# GSServer.net
KiCad netlist of a schematic drawn in EAGLE
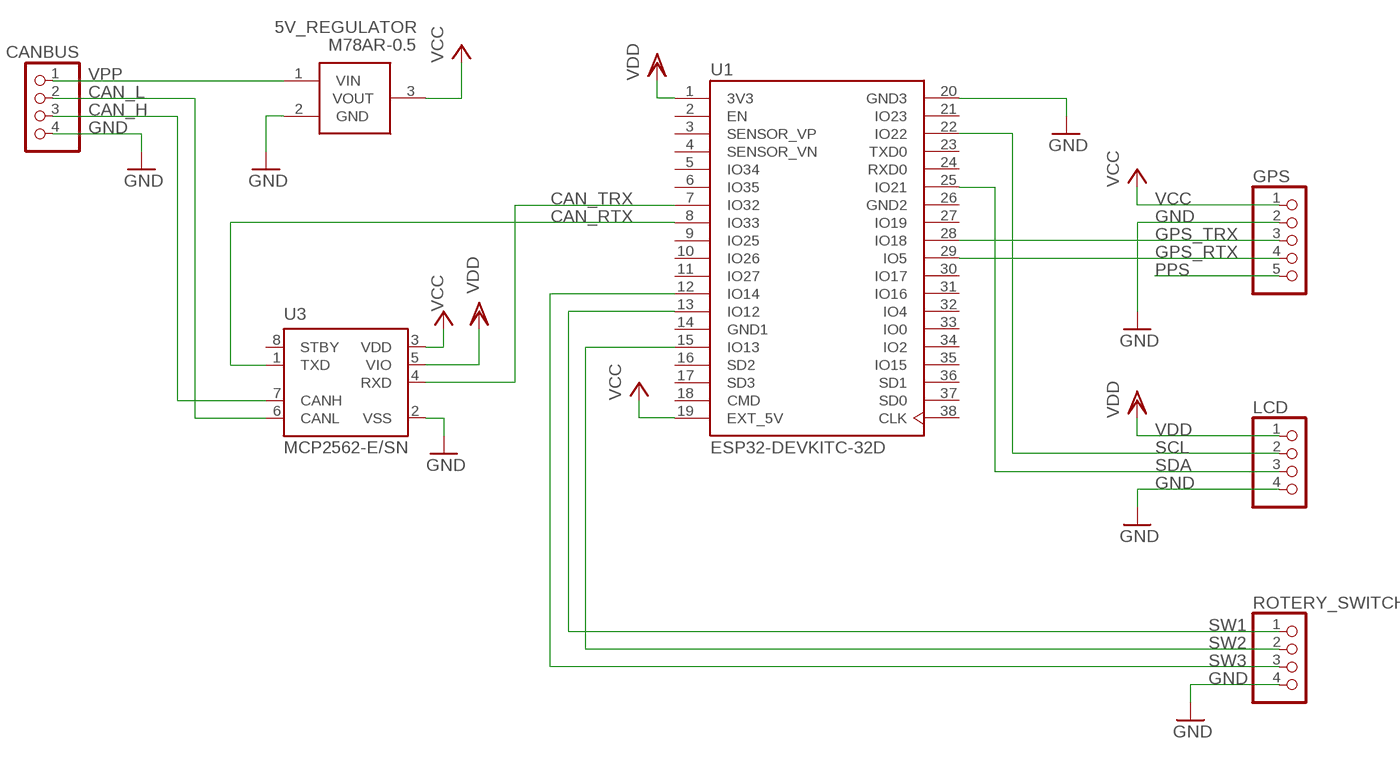
[diagram p0: schematic, sheet 1]

(export (version "E")
  (design (tool "Eeschema 10.0.6"))
  (components
    (comp (ref "5V_REGULATOR")
      (value "M78AR-0.5")
      (footprint "eagle-import:SHDR3W75P0X254_1X3_1128X755X10")
      (libsource (lib "eagle-import") (part "M78AR-0.5"))
    )
    (comp (ref "CANBUS")
      (value "PINHD-1X4")
      (footprint "eagle-import:1X04")
      (libsource (lib "eagle-import") (part "PINHD-1X4"))
    )
    (comp (ref "GPS")
      (value "PINHD-1X5")
      (footprint "eagle-import:1X05")
      (libsource (lib "eagle-import") (part "PINHD-1X5"))
    )
    (comp (ref "LCD")
      (value "PINHD-1X4")
      (footprint "eagle-import:1X04")
      (libsource (lib "eagle-import") (part "PINHD-1X4"))
    )
    (comp (ref "ROTERY_SWITCH")
      (value "PINHD-1X4")
      (footprint "eagle-import:1X04")
      (libsource (lib "eagle-import") (part "PINHD-1X4"))
    )
    (comp (ref "U1")
      (value "ESP32-DEVKITC-32D")
      (footprint "eagle-import:MODULE_ESP32-DEVKITC-32D")
      (fields (field (name "MF") "Espressif Systems"))
      (libsource (lib "eagle-import") (part "ESP32-DEVKITC-32D"))
    )
    (comp (ref "U3")
      (value "MCP2562-E/SN")
      (footprint "eagle-import:SOIC127P600X175-8N")
      (fields (field (name "MF") "Microchip"))
      (libsource (lib "eagle-import") (part "MCP2562-E/SN"))
    )
  )
  (nets
    (net (code "1") (name "/CAN_H") (class "Default")
      (node (ref "CANBUS") (pin "3") (pinfunction "3_3") (pintype "passive"))
      (node (ref "U3") (pin "7") (pinfunction "CANH_7") (pintype "input"))
    )
    (net (code "2") (name "/CAN_L") (class "Default")
      (node (ref "CANBUS") (pin "2") (pinfunction "2_2") (pintype "passive"))
      (node (ref "U3") (pin "6") (pinfunction "CANL_6") (pintype "input"))
    )
    (net (code "3") (name "/CAN_RTX") (class "Default")
      (node (ref "U1") (pin "8") (pinfunction "IO33_8") (pintype "bidirectional"))
      (node (ref "U3") (pin "1") (pinfunction "TXD_1") (pintype "input"))
    )
    (net (code "4") (name "/CAN_TRX") (class "Default")
      (node (ref "U1") (pin "7") (pinfunction "IO32_7") (pintype "bidirectional"))
      (node (ref "U3") (pin "4") (pinfunction "RXD_4") (pintype "output"))
    )
    (net (code "5") (name "/GND1") (class "Default")
      (node (ref "U1") (pin "14") (pinfunction "GND1_14") (pintype "power_in"))
    )
    (net (code "6") (name "/GND2") (class "Default")
      (node (ref "U1") (pin "26") (pinfunction "GND2_26") (pintype "power_in"))
    )
    (net (code "7") (name "/GPS_RTX") (class "Default")
      (node (ref "GPS") (pin "4") (pinfunction "4_4") (pintype "passive"))
      (node (ref "U1") (pin "29") (pinfunction "IO5_29") (pintype "bidirectional"))
    )
    (net (code "8") (name "/GPS_TRX") (class "Default")
      (node (ref "GPS") (pin "3") (pinfunction "3_3") (pintype "passive"))
      (node (ref "U1") (pin "28") (pinfunction "IO18_28") (pintype "bidirectional"))
    )
    (net (code "9") (name "/PPS") (class "Default")
      (node (ref "GPS") (pin "5") (pinfunction "5_5") (pintype "passive"))
    )
    (net (code "10") (name "/SCL") (class "Default")
      (node (ref "LCD") (pin "2") (pinfunction "2_2") (pintype "passive"))
      (node (ref "U1") (pin "22") (pinfunction "IO22_22") (pintype "bidirectional"))
    )
    (net (code "11") (name "/SDA") (class "Default")
      (node (ref "LCD") (pin "3") (pinfunction "3_3") (pintype "passive"))
      (node (ref "U1") (pin "25") (pinfunction "IO21_25") (pintype "bidirectional"))
    )
    (net (code "12") (name "/SW1") (class "Default")
      (node (ref "ROTERY_SWITCH") (pin "1") (pinfunction "1_1") (pintype "passive"))
      (node (ref "U1") (pin "13") (pinfunction "IO12_13") (pintype "bidirectional"))
    )
    (net (code "13") (name "/SW2") (class "Default")
      (node (ref "ROTERY_SWITCH") (pin "2") (pinfunction "2_2") (pintype "passive"))
      (node (ref "U1") (pin "15") (pinfunction "IO13_15") (pintype "bidirectional"))
    )
    (net (code "14") (name "/SW3") (class "Default")
      (node (ref "ROTERY_SWITCH") (pin "3") (pinfunction "3_3") (pintype "passive"))
      (node (ref "U1") (pin "12") (pinfunction "IO14_12") (pintype "bidirectional"))
    )
    (net (code "15") (name "/VPP") (class "Default")
      (node (ref "5V_REGULATOR") (pin "1") (pinfunction "VIN_1") (pintype "power_in"))
      (node (ref "CANBUS") (pin "1") (pinfunction "1_1") (pintype "passive"))
    )
    (net (code "16") (name "GND") (class "Default")
      (node (ref "5V_REGULATOR") (pin "2") (pinfunction "GND_2") (pintype "power_in"))
      (node (ref "CANBUS") (pin "4") (pinfunction "4_4") (pintype "passive"))
      (node (ref "GPS") (pin "2") (pinfunction "2_2") (pintype "passive"))
      (node (ref "LCD") (pin "4") (pinfunction "4_4") (pintype "passive"))
      (node (ref "ROTERY_SWITCH") (pin "4") (pinfunction "4_4") (pintype "passive"))
      (node (ref "U1") (pin "20") (pinfunction "GND3_20") (pintype "power_in"))
      (node (ref "U3") (pin "2") (pinfunction "VSS_2") (pintype "power_in"))
    )
    (net (code "17") (name "VCC") (class "Default")
      (node (ref "5V_REGULATOR") (pin "3") (pinfunction "VOUT_3") (pintype "power_in"))
      (node (ref "GPS") (pin "1") (pinfunction "1_1") (pintype "passive"))
      (node (ref "U1") (pin "19") (pinfunction "EXT_5V_19") (pintype "power_in"))
      (node (ref "U3") (pin "3") (pinfunction "VDD_3") (pintype "power_in"))
    )
    (net (code "18") (name "VDD") (class "Default")
      (node (ref "LCD") (pin "1") (pinfunction "1_1") (pintype "passive"))
      (node (ref "U1") (pin "1") (pinfunction "3V3_1") (pintype "power_in"))
      (node (ref "U3") (pin "5") (pinfunction "VIO_5") (pintype "power_in"))
    )
    (net (code "19") (name "unconnected-(U1-CLK-Pad38)") (class "Default")
      (node (ref "U1") (pin "38") (pinfunction "CLK_38") (pintype "input"))
    )
    (net (code "20") (name "unconnected-(U1-CMD-Pad18)") (class "Default")
      (node (ref "U1") (pin "18") (pinfunction "CMD_18") (pintype "bidirectional"))
    )
    (net (code "21") (name "unconnected-(U1-EN-Pad2)") (class "Default")
      (node (ref "U1") (pin "2") (pinfunction "EN_2") (pintype "input"))
    )
    (net (code "22") (name "unconnected-(U1-IO0-Pad33)") (class "Default")
      (node (ref "U1") (pin "33") (pinfunction "IO0_33") (pintype "bidirectional"))
    )
    (net (code "23") (name "unconnected-(U1-IO2-Pad34)") (class "Default")
      (node (ref "U1") (pin "34") (pinfunction "IO2_34") (pintype "bidirectional"))
    )
    (net (code "24") (name "unconnected-(U1-IO4-Pad32)") (class "Default")
      (node (ref "U1") (pin "32") (pinfunction "IO4_32") (pintype "bidirectional"))
    )
    (net (code "25") (name "unconnected-(U1-IO15-Pad35)") (class "Default")
      (node (ref "U1") (pin "35") (pinfunction "IO15_35") (pintype "bidirectional"))
    )
    (net (code "26") (name "unconnected-(U1-IO16-Pad31)") (class "Default")
      (node (ref "U1") (pin "31") (pinfunction "IO16_31") (pintype "bidirectional"))
    )
    (net (code "27") (name "unconnected-(U1-IO17-Pad30)") (class "Default")
      (node (ref "U1") (pin "30") (pinfunction "IO17_30") (pintype "bidirectional"))
    )
    (net (code "28") (name "unconnected-(U1-IO19-Pad27)") (class "Default")
      (node (ref "U1") (pin "27") (pinfunction "IO19_27") (pintype "bidirectional"))
    )
    (net (code "29") (name "unconnected-(U1-IO23-Pad21)") (class "Default")
      (node (ref "U1") (pin "21") (pinfunction "IO23_21") (pintype "bidirectional"))
    )
    (net (code "30") (name "unconnected-(U1-IO25-Pad9)") (class "Default")
      (node (ref "U1") (pin "9") (pinfunction "IO25_9") (pintype "bidirectional"))
    )
    (net (code "31") (name "unconnected-(U1-IO26-Pad10)") (class "Default")
      (node (ref "U1") (pin "10") (pinfunction "IO26_10") (pintype "bidirectional"))
    )
    (net (code "32") (name "unconnected-(U1-IO27-Pad11)") (class "Default")
      (node (ref "U1") (pin "11") (pinfunction "IO27_11") (pintype "bidirectional"))
    )
    (net (code "33") (name "unconnected-(U1-IO34-Pad5)") (class "Default")
      (node (ref "U1") (pin "5") (pinfunction "IO34_5") (pintype "bidirectional"))
    )
    (net (code "34") (name "unconnected-(U1-IO35-Pad6)") (class "Default")
      (node (ref "U1") (pin "6") (pinfunction "IO35_6") (pintype "bidirectional"))
    )
    (net (code "35") (name "unconnected-(U1-RXD0-Pad24)") (class "Default")
      (node (ref "U1") (pin "24") (pinfunction "RXD0_24") (pintype "input"))
    )
    (net (code "36") (name "unconnected-(U1-SD0-Pad37)") (class "Default")
      (node (ref "U1") (pin "37") (pinfunction "SD0_37") (pintype "bidirectional"))
    )
    (net (code "37") (name "unconnected-(U1-SD1-Pad36)") (class "Default")
      (node (ref "U1") (pin "36") (pinfunction "SD1_36") (pintype "bidirectional"))
    )
    (net (code "38") (name "unconnected-(U1-SD2-Pad16)") (class "Default")
      (node (ref "U1") (pin "16") (pinfunction "SD2_16") (pintype "bidirectional"))
    )
    (net (code "39") (name "unconnected-(U1-SD3-Pad17)") (class "Default")
      (node (ref "U1") (pin "17") (pinfunction "SD3_17") (pintype "bidirectional"))
    )
    (net (code "40") (name "unconnected-(U1-SENSOR_VN-Pad4)") (class "Default")
      (node (ref "U1") (pin "4") (pinfunction "SENSOR_VN_4") (pintype "input"))
    )
    (net (code "41") (name "unconnected-(U1-SENSOR_VP-Pad3)") (class "Default")
      (node (ref "U1") (pin "3") (pinfunction "SENSOR_VP_3") (pintype "input"))
    )
    (net (code "42") (name "unconnected-(U1-TXD0-Pad23)") (class "Default")
      (node (ref "U1") (pin "23") (pinfunction "TXD0_23") (pintype "output"))
    )
    (net (code "43") (name "unconnected-(U3-STBY-Pad8)") (class "Default")
      (node (ref "U3") (pin "8") (pinfunction "STBY_8") (pintype "input"))
    )
  )
)
